# DaviShematic.net
KiCad netlist of a schematic drawn in EAGLE
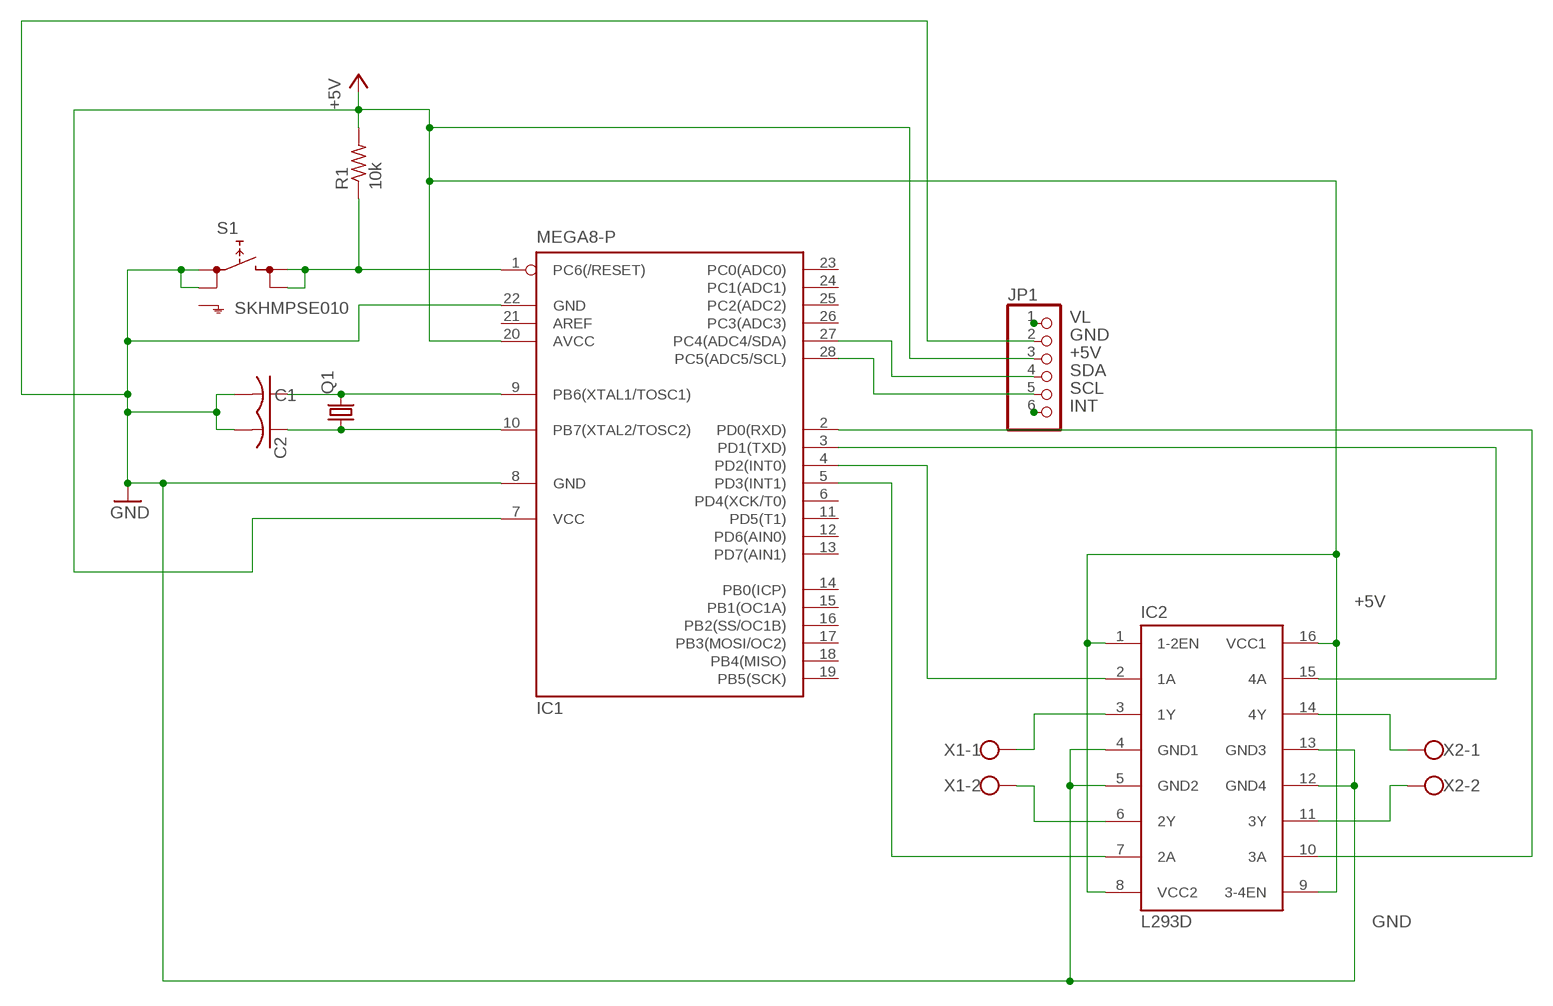
[diagram p0: schematic, sheet 1]

(export (version "E")
  (design (tool "Eeschema 10.0.6"))
  (components
    (comp (ref "C1")
      (value "C-US025-024X044")
      (footprint "eagle-import:C025-024X044")
      (libsource (lib "eagle-import") (part "C-US025-024X044"))
    )
    (comp (ref "C2")
      (value "C-US025-024X044")
      (footprint "eagle-import:C025-024X044")
      (libsource (lib "eagle-import") (part "C-US025-024X044"))
    )
    (comp (ref "IC1")
      (value "MEGA8-P")
      (footprint "eagle-import:DIL28-3")
      (libsource (lib "eagle-import") (part "MEGA8-P"))
    )
    (comp (ref "IC2")
      (value "L293D")
      (footprint "eagle-import:DIL16")
      (libsource (lib "eagle-import") (part "L293D"))
    )
    (comp (ref "JP1")
      (value "PINHD-1X6")
      (footprint "eagle-import:1X06")
      (libsource (lib "eagle-import") (part "PINHD-1X6"))
    )
    (comp (ref "Q1")
      (value "CRYSTALHC49U-V")
      (footprint "eagle-import:HC49U-V")
      (libsource (lib "eagle-import") (part "CRYSTALHC49U-V"))
    )
    (comp (ref "R1")
      (value "10k")
      (footprint "eagle-import:0207_7")
      (libsource (lib "eagle-import") (part "R-US_0207/7"))
    )
    (comp (ref "S1")
      (value "SKHMPSE010")
      (footprint "eagle-import:SKHMPXE010")
      (libsource (lib "eagle-import") (part "SKHMPE010S"))
    )
    (comp (ref "X1")
      (value "W237-102")
      (footprint "eagle-import:W237-102")
      (fields (field (name "MPN") "237-102"))
      (libsource (lib "eagle-import") (part "W237-102"))
    )
    (comp (ref "X2")
      (value "W237-102")
      (footprint "eagle-import:W237-102")
      (fields (field (name "MPN") "237-102"))
      (libsource (lib "eagle-import") (part "W237-102"))
    )
  )
  (nets
    (net (code "1") (name "+5V") (class "Default")
      (node (ref "IC1") (pin "20") (pinfunction "AVCC_20") (pintype "power_in"))
      (node (ref "IC1") (pin "7") (pinfunction "VCC_7") (pintype "power_in"))
      (node (ref "IC2") (pin "1") (pinfunction "1-2EN_1") (pintype "input"))
      (node (ref "IC2") (pin "16") (pinfunction "VCC1_16") (pintype "power_in"))
      (node (ref "IC2") (pin "8") (pinfunction "VCC2_8") (pintype "power_in"))
      (node (ref "IC2") (pin "9") (pinfunction "3-4EN_9") (pintype "input"))
      (node (ref "JP1") (pin "3") (pinfunction "3_3") (pintype "passive"))
      (node (ref "R1") (pin "2") (pinfunction "2_2") (pintype "passive"))
    )
    (net (code "2") (name "/INT") (class "Default")
      (node (ref "JP1") (pin "6") (pinfunction "6_6") (pintype "passive"))
    )
    (net (code "3") (name "/SCL") (class "Default")
      (node (ref "IC1") (pin "28") (pinfunction "PC5(ADC5/SCL)_28") (pintype "bidirectional"))
      (node (ref "JP1") (pin "5") (pinfunction "5_5") (pintype "passive"))
    )
    (net (code "4") (name "/SDA") (class "Default")
      (node (ref "IC1") (pin "27") (pinfunction "PC4(ADC4/SDA)_27") (pintype "bidirectional"))
      (node (ref "JP1") (pin "4") (pinfunction "4_4") (pintype "passive"))
    )
    (net (code "5") (name "/VL") (class "Default")
      (node (ref "JP1") (pin "1") (pinfunction "1_1") (pintype "passive"))
    )
    (net (code "6") (name "GND") (class "Default")
      (node (ref "C1") (pin "2") (pinfunction "2_2") (pintype "passive"))
      (node (ref "C2") (pin "2") (pinfunction "2_2") (pintype "passive"))
      (node (ref "IC1") (pin "22") (pinfunction "GND_22") (pintype "power_in"))
      (node (ref "IC1") (pin "8") (pinfunction "GND_8") (pintype "power_in"))
      (node (ref "IC2") (pin "12") (pinfunction "GND4_12") (pintype "power_in"))
      (node (ref "IC2") (pin "13") (pinfunction "GND3_13") (pintype "power_in"))
      (node (ref "IC2") (pin "4") (pinfunction "GND1_4") (pintype "power_in"))
      (node (ref "IC2") (pin "5") (pinfunction "GND2_5") (pintype "power_in"))
      (node (ref "JP1") (pin "2") (pinfunction "2_2") (pintype "passive"))
      (node (ref "S1") (pin "1") (pinfunction "1.1_1") (pintype "passive"))
      (node (ref "S1") (pin "2") (pinfunction "1.2_2") (pintype "passive"))
    )
    (net (code "7") (name "Net-(IC1-PB6(XTAL1{slash}TOSC1))") (class "Default")
      (node (ref "C1") (pin "1") (pinfunction "1_1") (pintype "passive"))
      (node (ref "IC1") (pin "9") (pinfunction "PB6(XTAL1/TOSC1)_9") (pintype "bidirectional"))
      (node (ref "Q1") (pin "2") (pinfunction "2_2") (pintype "passive"))
    )
    (net (code "8") (name "Net-(IC1-PB7(XTAL2{slash}TOSC2))") (class "Default")
      (node (ref "C2") (pin "1") (pinfunction "1_1") (pintype "passive"))
      (node (ref "IC1") (pin "10") (pinfunction "PB7(XTAL2/TOSC2)_10") (pintype "bidirectional"))
      (node (ref "Q1") (pin "1") (pinfunction "1_1") (pintype "passive"))
    )
    (net (code "9") (name "Net-(IC1-PC6({slash}RESET))") (class "Default")
      (node (ref "IC1") (pin "1") (pinfunction "PC6(/RESET)_1") (pintype "bidirectional"))
      (node (ref "R1") (pin "1") (pinfunction "1_1") (pintype "passive"))
      (node (ref "S1") (pin "3") (pinfunction "2.1_3") (pintype "passive"))
      (node (ref "S1") (pin "4") (pinfunction "2.2_4") (pintype "passive"))
    )
    (net (code "10") (name "Net-(IC1-PD0(RXD))") (class "Default")
      (node (ref "IC1") (pin "2") (pinfunction "PD0(RXD)_2") (pintype "bidirectional"))
      (node (ref "IC2") (pin "10") (pinfunction "3A_10") (pintype "input"))
    )
    (net (code "11") (name "Net-(IC1-PD1(TXD))") (class "Default")
      (node (ref "IC1") (pin "3") (pinfunction "PD1(TXD)_3") (pintype "bidirectional"))
      (node (ref "IC2") (pin "15") (pinfunction "4A_15") (pintype "input"))
    )
    (net (code "12") (name "Net-(IC1-PD2(INT0))") (class "Default")
      (node (ref "IC1") (pin "4") (pinfunction "PD2(INT0)_4") (pintype "bidirectional"))
      (node (ref "IC2") (pin "2") (pinfunction "1A_2") (pintype "input"))
    )
    (net (code "13") (name "Net-(IC1-PD3(INT1))") (class "Default")
      (node (ref "IC1") (pin "5") (pinfunction "PD3(INT1)_5") (pintype "bidirectional"))
      (node (ref "IC2") (pin "7") (pinfunction "2A_7") (pintype "input"))
    )
    (net (code "14") (name "Net-(IC2-1Y)") (class "Default")
      (node (ref "IC2") (pin "3") (pinfunction "1Y_3") (pintype "output"))
      (node (ref "X1") (pin "1") (pinfunction "KL_1") (pintype "passive"))
    )
    (net (code "15") (name "Net-(IC2-2Y)") (class "Default")
      (node (ref "IC2") (pin "6") (pinfunction "2Y_6") (pintype "output"))
      (node (ref "X1") (pin "2") (pinfunction "KL_2") (pintype "passive"))
    )
    (net (code "16") (name "Net-(IC2-3Y)") (class "Default")
      (node (ref "IC2") (pin "11") (pinfunction "3Y_11") (pintype "output"))
      (node (ref "X2") (pin "2") (pinfunction "KL_2") (pintype "passive"))
    )
    (net (code "17") (name "Net-(IC2-4Y)") (class "Default")
      (node (ref "IC2") (pin "14") (pinfunction "4Y_14") (pintype "output"))
      (node (ref "X2") (pin "1") (pinfunction "KL_1") (pintype "passive"))
    )
    (net (code "18") (name "unconnected-(IC1-AREF-Pad21)") (class "Default")
      (node (ref "IC1") (pin "21") (pinfunction "AREF_21") (pintype "passive"))
    )
    (net (code "19") (name "unconnected-(IC1-PB0(ICP)-Pad14)") (class "Default")
      (node (ref "IC1") (pin "14") (pinfunction "PB0(ICP)_14") (pintype "bidirectional"))
    )
    (net (code "20") (name "unconnected-(IC1-PB1(OC1A)-Pad15)") (class "Default")
      (node (ref "IC1") (pin "15") (pinfunction "PB1(OC1A)_15") (pintype "bidirectional"))
    )
    (net (code "21") (name "unconnected-(IC1-PB2(SS{slash}OC1B)-Pad16)") (class "Default")
      (node (ref "IC1") (pin "16") (pinfunction "PB2(SS/OC1B)_16") (pintype "bidirectional"))
    )
    (net (code "22") (name "unconnected-(IC1-PB3(MOSI{slash}OC2)-Pad17)") (class "Default")
      (node (ref "IC1") (pin "17") (pinfunction "PB3(MOSI/OC2)_17") (pintype "bidirectional"))
    )
    (net (code "23") (name "unconnected-(IC1-PB4(MISO)-Pad18)") (class "Default")
      (node (ref "IC1") (pin "18") (pinfunction "PB4(MISO)_18") (pintype "bidirectional"))
    )
    (net (code "24") (name "unconnected-(IC1-PB5(SCK)-Pad19)") (class "Default")
      (node (ref "IC1") (pin "19") (pinfunction "PB5(SCK)_19") (pintype "bidirectional"))
    )
    (net (code "25") (name "unconnected-(IC1-PC0(ADC0)-Pad23)") (class "Default")
      (node (ref "IC1") (pin "23") (pinfunction "PC0(ADC0)_23") (pintype "bidirectional"))
    )
    (net (code "26") (name "unconnected-(IC1-PC1(ADC1)-Pad24)") (class "Default")
      (node (ref "IC1") (pin "24") (pinfunction "PC1(ADC1)_24") (pintype "bidirectional"))
    )
    (net (code "27") (name "unconnected-(IC1-PC2(ADC2)-Pad25)") (class "Default")
      (node (ref "IC1") (pin "25") (pinfunction "PC2(ADC2)_25") (pintype "bidirectional"))
    )
    (net (code "28") (name "unconnected-(IC1-PC3(ADC3)-Pad26)") (class "Default")
      (node (ref "IC1") (pin "26") (pinfunction "PC3(ADC3)_26") (pintype "bidirectional"))
    )
    (net (code "29") (name "unconnected-(IC1-PD4(XCK{slash}T0)-Pad6)") (class "Default")
      (node (ref "IC1") (pin "6") (pinfunction "PD4(XCK/T0)_6") (pintype "bidirectional"))
    )
    (net (code "30") (name "unconnected-(IC1-PD5(T1)-Pad11)") (class "Default")
      (node (ref "IC1") (pin "11") (pinfunction "PD5(T1)_11") (pintype "bidirectional"))
    )
    (net (code "31") (name "unconnected-(IC1-PD6(AIN0)-Pad12)") (class "Default")
      (node (ref "IC1") (pin "12") (pinfunction "PD6(AIN0)_12") (pintype "bidirectional"))
    )
    (net (code "32") (name "unconnected-(IC1-PD7(AIN1)-Pad13)") (class "Default")
      (node (ref "IC1") (pin "13") (pinfunction "PD7(AIN1)_13") (pintype "bidirectional"))
    )
    (net (code "33") (name "unconnected-(S1-SH-Pad5)") (class "Default")
      (node (ref "S1") (pin "5") (pinfunction "SH_5") (pintype "passive"))
    )
  )
)
